# NEW-AQB-5-ANTON_TRANS-PWR_MotionControll.net
KiCad netlist of a schematic drawn in Altium Designer
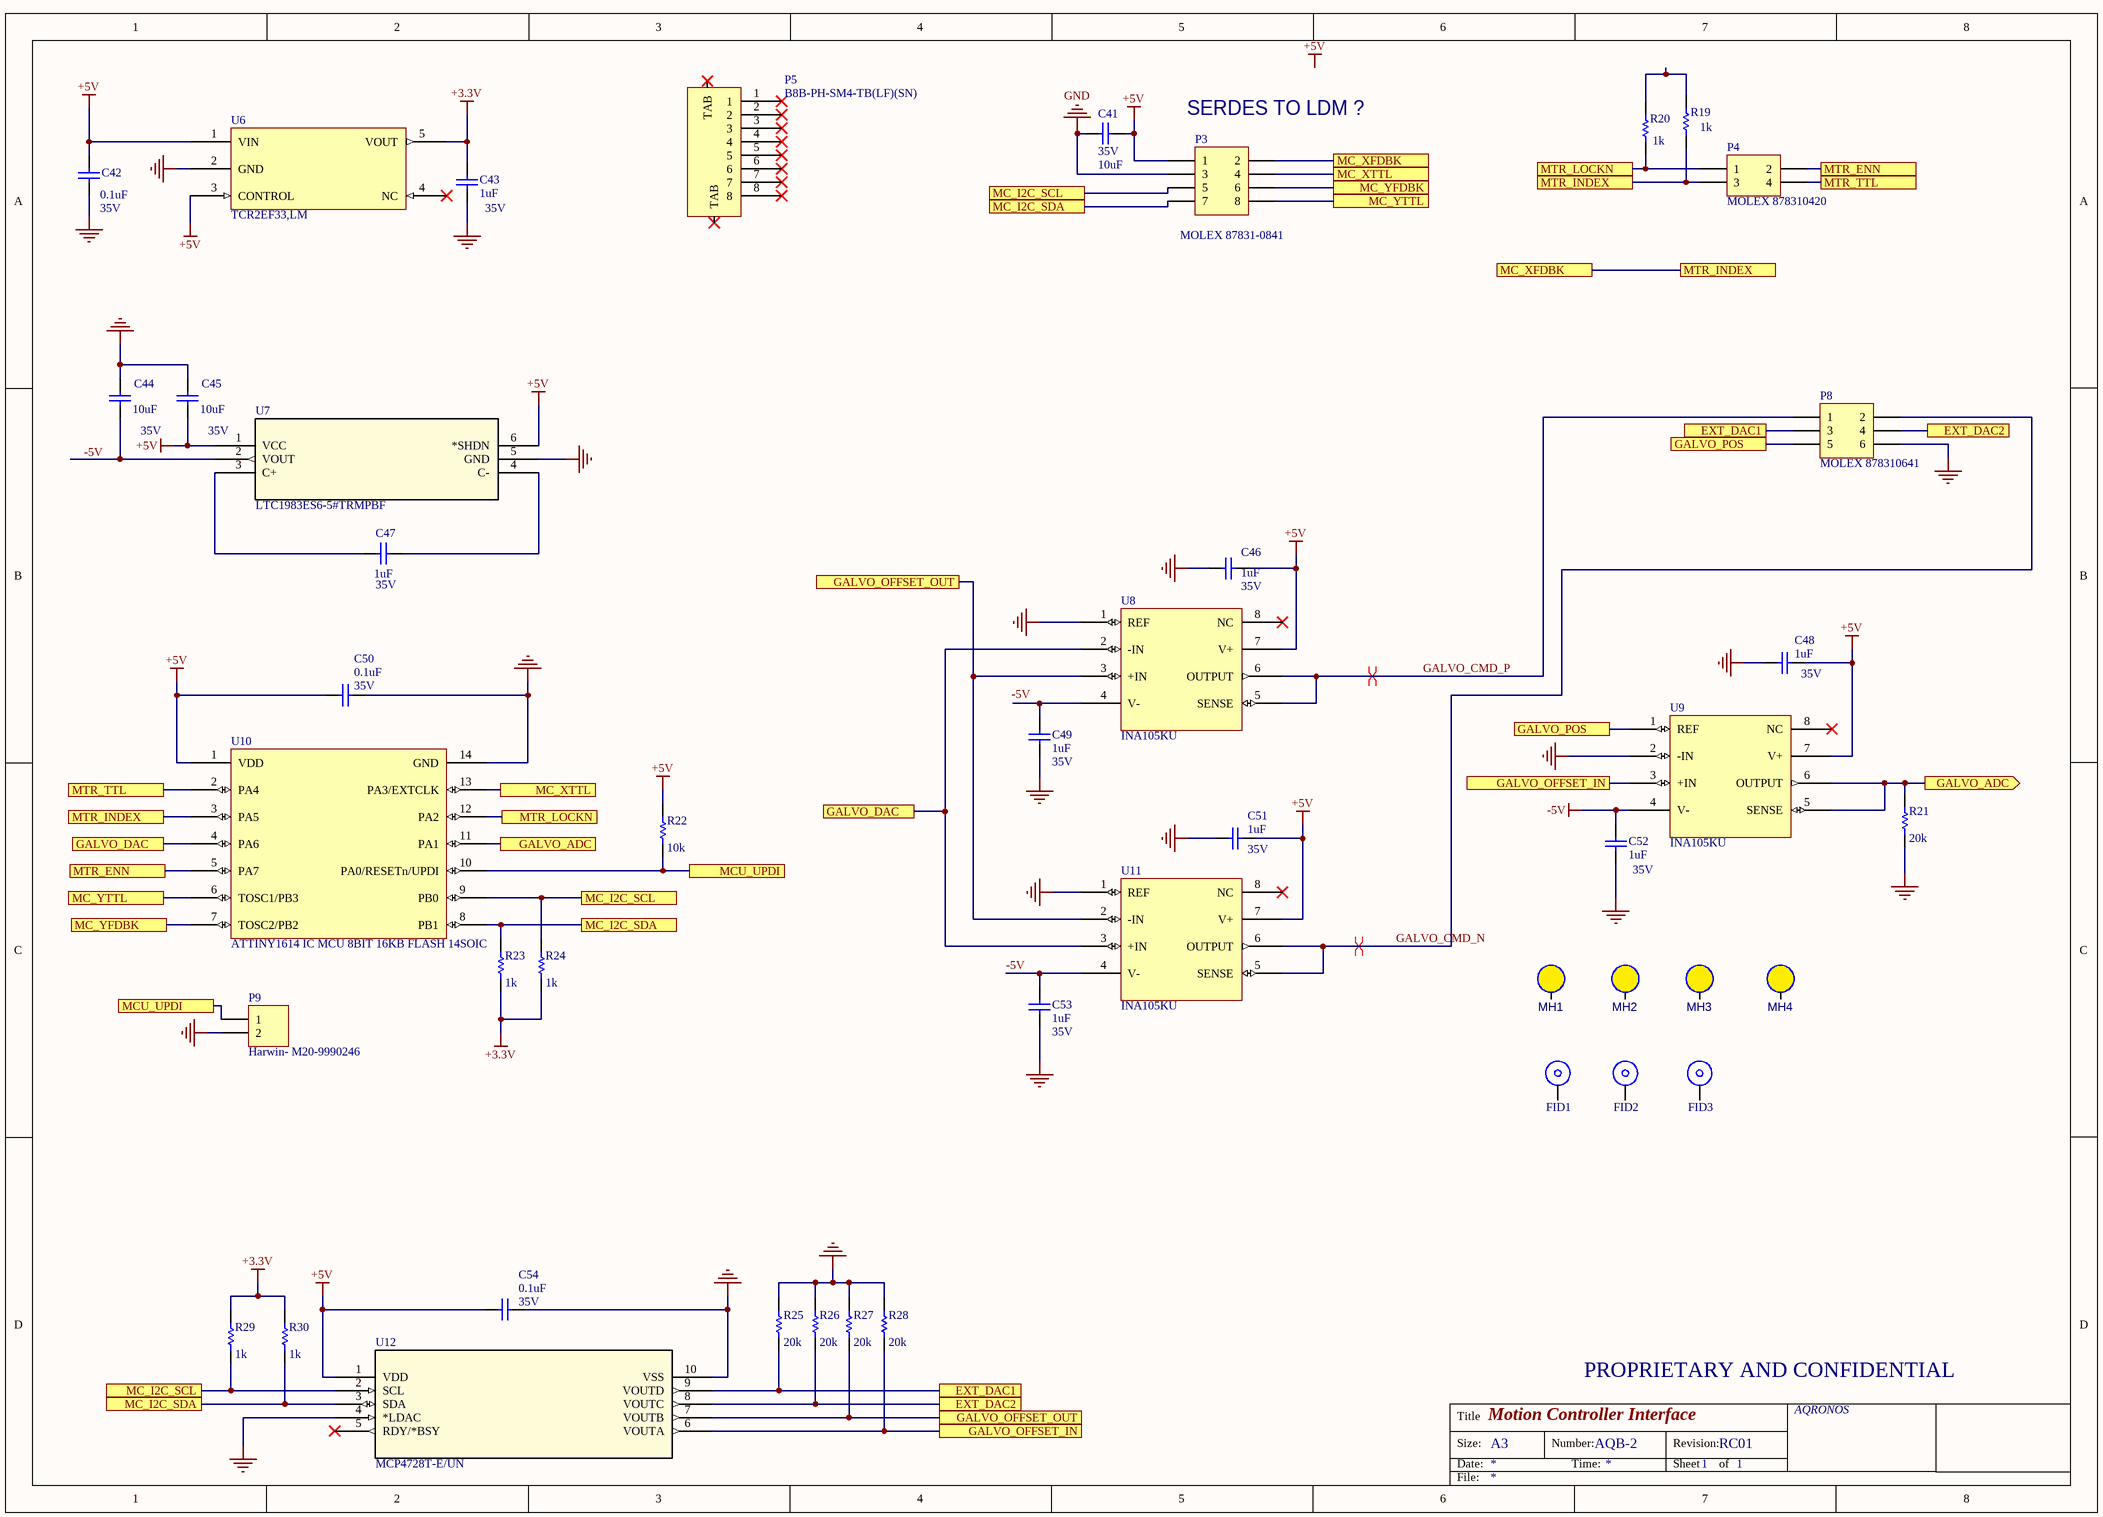
[diagram p0: NEW-AQB-5-ANTON_TRANS-PWR_MotionController.SchDoc]

(export (version "E")
  (design (tool "Eeschema 10.0.6"))
  (components
    (comp (ref "C41")
      (value "10uF")
      (footprint "CAP1206")
      (description "Capacitor_non_pol")
      (fields (field (name "MANUFACTURER PART NUMBER") "CGA5L1X7R1V106K160AC") (field (name "VOLTAGE") "35V"))
      (libsource (lib "AQRONOS_TEMP_SCH") (part "Capacitor_non_pol"))
    )
    (comp (ref "C42")
      (value "0.1uF")
      (footprint "CAP0402")
      (description "Capacitor_non_pol")
      (fields (field (name "MANUFACTURER PART NUMBER") "GMK107B7104KAHT") (field (name "VOLTAGE") "35V"))
      (libsource (lib "AQRONOS_TEMP_SCH") (part "Capacitor_non_pol"))
    )
    (comp (ref "C43")
      (value "1uF")
      (footprint "CAP0402")
      (description "Capacitor_non_pol")
      (fields (field (name "MANUFACTURER PART NUMBER") "GMK107AB7105KAHT") (field (name "VOLTAGE") "35V"))
      (libsource (lib "AQRONOS_TEMP_SCH") (part "Capacitor_non_pol"))
    )
    (comp (ref "C44")
      (value "10uF")
      (footprint "CAP1206")
      (description "Capacitor_non_pol")
      (fields (field (name "MANUFACTURER PART NUMBER") "CGA5L1X7R1V106K160AC") (field (name "VOLTAGE") "35V"))
      (libsource (lib "AQRONOS_TEMP_SCH") (part "Capacitor_non_pol"))
    )
    (comp (ref "C45")
      (value "10uF")
      (footprint "CAP1206")
      (description "Capacitor_non_pol")
      (fields (field (name "MANUFACTURER PART NUMBER") "CGA5L1X7R1V106K160AC") (field (name "VOLTAGE") "35V"))
      (libsource (lib "AQRONOS_TEMP_SCH") (part "Capacitor_non_pol"))
    )
    (comp (ref "C46")
      (value "1uF")
      (footprint "CAP0402")
      (description "Capacitor_non_pol")
      (fields (field (name "MANUFACTURER PART NUMBER") "GMK107AB7105KAHT") (field (name "VOLTAGE") "35V"))
      (libsource (lib "AQRONOS_TEMP_SCH") (part "Capacitor_non_pol"))
    )
    (comp (ref "C47")
      (value "1uF")
      (footprint "CAP0402")
      (description "Capacitor_non_pol")
      (fields (field (name "MANUFACTURER PART NUMBER") "GMK107AB7105KAHT") (field (name "VOLTAGE") "35V"))
      (libsource (lib "AQRONOS_TEMP_SCH") (part "Capacitor_non_pol"))
    )
    (comp (ref "C48")
      (value "1uF")
      (footprint "CAP0402")
      (description "Capacitor_non_pol")
      (fields (field (name "MANUFACTURER PART NUMBER") "GMK107AB7105KAHT") (field (name "VOLTAGE") "35V"))
      (libsource (lib "AQRONOS_TEMP_SCH") (part "Capacitor_non_pol"))
    )
    (comp (ref "C49")
      (value "1uF")
      (footprint "CAP0402")
      (description "Capacitor_non_pol")
      (fields (field (name "MANUFACTURER PART NUMBER") "GMK107AB7105KAHT") (field (name "VOLTAGE") "35V"))
      (libsource (lib "AQRONOS_TEMP_SCH") (part "Capacitor_non_pol"))
    )
    (comp (ref "C50")
      (value "0.1uF")
      (footprint "CAP0402")
      (description "Capacitor_non_pol")
      (fields (field (name "MANUFACTURER PART NUMBER") "GMK107B7104KAHT") (field (name "VOLTAGE") "35V"))
      (libsource (lib "AQRONOS_TEMP_SCH") (part "Capacitor_non_pol"))
    )
    (comp (ref "C51")
      (value "1uF")
      (footprint "CAP0402")
      (description "Capacitor_non_pol")
      (fields (field (name "MANUFACTURER PART NUMBER") "GMK107AB7105KAHT") (field (name "VOLTAGE") "35V"))
      (libsource (lib "AQRONOS_TEMP_SCH") (part "Capacitor_non_pol"))
    )
    (comp (ref "C52")
      (value "1uF")
      (footprint "CAP0402")
      (description "Capacitor_non_pol")
      (fields (field (name "MANUFACTURER PART NUMBER") "GMK107AB7105KAHT") (field (name "VOLTAGE") "35V"))
      (libsource (lib "AQRONOS_TEMP_SCH") (part "Capacitor_non_pol"))
    )
    (comp (ref "C53")
      (value "1uF")
      (footprint "CAP0402")
      (description "Capacitor_non_pol")
      (fields (field (name "MANUFACTURER PART NUMBER") "GMK107AB7105KAHT") (field (name "VOLTAGE") "35V"))
      (libsource (lib "AQRONOS_TEMP_SCH") (part "Capacitor_non_pol"))
    )
    (comp (ref "C54")
      (value "0.1uF")
      (footprint "CAP0402")
      (description "Capacitor_non_pol")
      (fields (field (name "MANUFACTURER PART NUMBER") "GMK107B7104KAHT") (field (name "VOLTAGE") "35V"))
      (libsource (lib "AQRONOS_TEMP_SCH") (part "Capacitor_non_pol"))
    )
    (comp (ref "FID1")
      (value "FIDUCIAL")
      (footprint "FID")
      (description "FID")
      (libsource (lib "AQRONOS-Released") (part "FID"))
    )
    (comp (ref "FID2")
      (value "FIDUCIAL")
      (footprint "FID")
      (description "FID")
      (libsource (lib "AQRONOS-Released") (part "FID"))
    )
    (comp (ref "FID3")
      (value "FIDUCIAL")
      (footprint "FID")
      (description "FID")
      (libsource (lib "AQRONOS-Released") (part "FID"))
    )
    (comp (ref "MH1")
      (value "PAD-MH")
      (footprint "PAD-135Mils")
      (description "PAD,MOUNTING HOLE")
      (libsource (lib "AQRONOS-Released") (part "PAD-MH"))
    )
    (comp (ref "MH2")
      (value "PAD-MH")
      (footprint "PAD-135Mils")
      (description "PAD,MOUNTING HOLE")
      (libsource (lib "AQRONOS-Released") (part "PAD-MH"))
    )
    (comp (ref "MH3")
      (value "PAD-MH")
      (footprint "PAD-135Mils")
      (description "PAD,MOUNTING HOLE")
      (libsource (lib "AQRONOS-Released") (part "PAD-MH"))
    )
    (comp (ref "MH4")
      (value "PAD-MH")
      (footprint "PAD-135Mils")
      (description "PAD,MOUNTING HOLE")
      (libsource (lib "AQRONOS-Released") (part "PAD-MH"))
    )
    (comp (ref "P3")
      (value "MOLEX 87831-0841")
      (footprint "HDR4X2-Molex")
      (description "Connector Header Through Hole 8 position 0.079\" (2.00mm)")
      (fields
        (field (name "DIGI-KEY PART NUMBER") "WM8611-ND")
        (field (name "MANUFACTURER PART NUMBER") "0878310841")
      )
      (libsource (lib "AQRONOS-Released") (part "HDR4x2-87831-0841"))
    )
    (comp (ref "P4")
      (value "MOLEX 878310420")
      (footprint "HDR2X2-Molex")
      (description "Connector Header Through Hole 4 position 0.079\" (2.00mm)")
      (fields
        (field (name "DIGI-KEY PART NUMBER") "WM18557-ND")
        (field (name "MANUFACTURER PART NUMBER") "87831-0420")
      )
      (libsource (lib "AQRONOS-Released") (part "HDR2x2-878310420"))
    )
    (comp (ref "P5")
      (value "B8B-PH-SM4-TB(LF)(SN)")
      (footprint "B8B-PH-SM4-TB(LF)(SN)")
      (description "8 PIN JST SMT 2.0 MM PITCH")
      (libsource (lib "AQRONOS_TEMP_SCH") (part "B8B-PH-SM4-TB(LF)(SN)"))
    )
    (comp (ref "P8")
      (value "MOLEX 878310641")
      (footprint "HDR3X2-Molex")
      (description "Connector Header Through Hole 6 position 0.079\" (2.00mm)")
      (fields
        (field (name "DIGI-KEY PART NUMBER") "WM3590-ND")
        (field (name "MANUFACTURER PART NUMBER") "878310641")
      )
      (libsource (lib "AQRONOS-Released") (part "HDR3x2-878310641"))
    )
    (comp (ref "P9")
      (value "Harwin- M20-9990246")
      (footprint "HDR1X2")
      (description "Connector Header Through Hole 2 position 0.100\" (2.54mm)")
      (fields
        (field (name "DIGI-KEY PART NUMBER") "952-2262-ND")
        (field (name "MANUFACTURER PART NUMBER") "M20-9990246")
      )
      (libsource (lib "AQRONOS-Released") (part "HDR1x2-M20-9990246"))
    )
    (comp (ref "R19")
      (value "1k")
      (footprint "RES0402")
      (description "Resistor")
      (fields (field (name "MANUFACTURER PART NUMBER") "ERJ-2GEJ102X"))
      (libsource (lib "AQRONOS_TEMP_SCH") (part "Resistor"))
    )
    (comp (ref "R20")
      (value "1k")
      (footprint "RES0402")
      (description "Resistor")
      (fields (field (name "MANUFACTURER PART NUMBER") "ERJ-2GEJ102X"))
      (libsource (lib "AQRONOS_TEMP_SCH") (part "Resistor"))
    )
    (comp (ref "R21")
      (value "20k")
      (footprint "RES0402")
      (description "Resistor")
      (fields (field (name "MANUFACTURER PART NUMBER") "ERJ-2RKF2002X"))
      (libsource (lib "AQRONOS_TEMP_SCH") (part "Resistor"))
    )
    (comp (ref "R22")
      (value "10k")
      (footprint "RES0402")
      (description "Resistor")
      (fields (field (name "MANUFACTURER PART NUMBER") "ERJ-2GEJ103X"))
      (libsource (lib "AQRONOS_TEMP_SCH") (part "Resistor"))
    )
    (comp (ref "R23")
      (value "1k")
      (footprint "RES0402")
      (description "Resistor")
      (fields (field (name "MANUFACTURER PART NUMBER") "ERJ-2GEJ102X"))
      (libsource (lib "AQRONOS_TEMP_SCH") (part "Resistor"))
    )
    (comp (ref "R24")
      (value "1k")
      (footprint "RES0402")
      (description "Resistor")
      (fields (field (name "MANUFACTURER PART NUMBER") "ERJ-2GEJ102X"))
      (libsource (lib "AQRONOS_TEMP_SCH") (part "Resistor"))
    )
    (comp (ref "R25")
      (value "20k")
      (footprint "RES0402")
      (description "Resistor")
      (fields (field (name "MANUFACTURER PART NUMBER") "ERJ-2RKF2002X"))
      (libsource (lib "AQRONOS_TEMP_SCH") (part "Resistor"))
    )
    (comp (ref "R26")
      (value "20k")
      (footprint "RES0402")
      (description "Resistor")
      (fields (field (name "MANUFACTURER PART NUMBER") "ERJ-2RKF2002X"))
      (libsource (lib "AQRONOS_TEMP_SCH") (part "Resistor"))
    )
    (comp (ref "R27")
      (value "20k")
      (footprint "RES0402")
      (description "Resistor")
      (fields (field (name "MANUFACTURER PART NUMBER") "ERJ-2RKF2002X"))
      (libsource (lib "AQRONOS_TEMP_SCH") (part "Resistor"))
    )
    (comp (ref "R28")
      (value "20k")
      (footprint "RES0402")
      (description "Resistor")
      (fields (field (name "MANUFACTURER PART NUMBER") "ERJ-2RKF2002X"))
      (libsource (lib "AQRONOS_TEMP_SCH") (part "Resistor"))
    )
    (comp (ref "R29")
      (value "1k")
      (footprint "RES0402")
      (description "Resistor")
      (fields (field (name "MANUFACTURER PART NUMBER") "ERJ-2GEJ102X"))
      (libsource (lib "AQRONOS_TEMP_SCH") (part "Resistor"))
    )
    (comp (ref "R30")
      (value "1k")
      (footprint "RES0402")
      (description "Resistor")
      (fields (field (name "MANUFACTURER PART NUMBER") "ERJ-2GEJ102X"))
      (libsource (lib "AQRONOS_TEMP_SCH") (part "Resistor"))
    )
    (comp (ref "U6")
      (value "TCR2EF33,LM")
      (footprint "SOT-753")
      (description "Linear Voltage Regulator IC Positive Fixed 1 Output 200mA SMV")
      (fields
        (field (name "DIGIKEY PART NUMBER") "TCR2EF33LM(CTTR-ND")
        (field (name "MANUFACTURER PART NUMBER") "TCR2EF33,LM(CT")
      )
      (libsource (lib "AQRONOS-Released") (part "TCR2EF33,LM"))
    )
    (comp (ref "U7")
      (value "LTC1983ES6-5#TRMPBF")
      (footprint "SOT-23-6")
      (description "Charge Pump Switching Regulator IC Negative Fixed -5V 1 Output 100mA SOT-23-6 Thin, TSOT-23-6")
      (fields (field (name "DIGI-KEY PART NUMBER") "LTC1983ES6-5#TRMPBFTR-ND"))
      (libsource (lib "AQRONOS-Released") (part "LTC1983ES6-5#TRM"))
    )
    (comp (ref "U8")
      (value "INA105KU")
      (footprint "SOIC8")
      (description "IC OPAMP DIFFERENTIAL 1MHZ 8SOIC")
      (fields (field (name "DIGI-KEY PART NUMBER") "296-44407-5-ND"))
      (libsource (lib "AQRONOS-Released") (part "INA105"))
    )
    (comp (ref "U9")
      (value "INA105KU")
      (footprint "SOIC8")
      (description "IC OPAMP DIFFERENTIAL 1MHZ 8SOIC")
      (fields (field (name "DIGI-KEY PART NUMBER") "296-44407-5-ND"))
      (libsource (lib "AQRONOS-Released") (part "INA105"))
    )
    (comp (ref "U10")
      (value "ATTINY1614 IC MCU 8BIT 16KB FLASH 14SOIC")
      (footprint "SOIC14")
      (description "AVR tinyAVR™ 1 Microcontroller IC 8-Bit 20MHz 16KB (16K x 8) FLASH 14-SOIC")
      (fields
        (field (name "DIGI-KEY PART NUMBER") "ATTINY1614-SSFRCT-ND")
        (field (name "MANUFACTURER PART NUMBER") "ATTINY1614-SSFR")
      )
      (libsource (lib "AQRONOS-Released") (part "ATTINY1614-SSFR"))
    )
    (comp (ref "U11")
      (value "INA105KU")
      (footprint "SOIC8")
      (description "IC OPAMP DIFFERENTIAL 1MHZ 8SOIC")
      (fields (field (name "DIGI-KEY PART NUMBER") "296-44407-5-ND"))
      (libsource (lib "AQRONOS-Released") (part "INA105"))
    )
    (comp (ref "U12")
      (value "MCP4728T-E/UN")
      (footprint "MSOP10")
      (description "12 Bit Digital to Analog Converter 4 10-MSOP")
      (fields (field (name "DIGI-KEY PART NUMBER") "MCP4728T-E/UNTR-ND"))
      (libsource (lib "AQRONOS-Released") (part "MCP4728T-E/UN"))
    )
  )
  (nets
    (net (code "1") (name "+3.3V") (class "Default")
      (node (ref "C43") (pin "1") (pinfunction "1_1") (pintype "passive"))
      (node (ref "R23") (pin "1") (pinfunction "1_1") (pintype "passive"))
      (node (ref "R24") (pin "1") (pinfunction "1_1") (pintype "passive"))
      (node (ref "R29") (pin "2") (pinfunction "2_2") (pintype "passive"))
      (node (ref "R30") (pin "2") (pinfunction "2_2") (pintype "passive"))
      (node (ref "U6") (pin "5") (pinfunction "VOUT_5") (pintype "output"))
    )
    (net (code "2") (name "+5V") (class "Default")
      (node (ref "C41") (pin "2") (pinfunction "2_2") (pintype "passive"))
      (node (ref "C42") (pin "1") (pinfunction "1_1") (pintype "passive"))
      (node (ref "C45") (pin "2") (pinfunction "2_2") (pintype "passive"))
      (node (ref "C46") (pin "2") (pinfunction "2_2") (pintype "passive"))
      (node (ref "C48") (pin "2") (pinfunction "2_2") (pintype "passive"))
      (node (ref "C50") (pin "2") (pinfunction "2_2") (pintype "passive"))
      (node (ref "C51") (pin "2") (pinfunction "2_2") (pintype "passive"))
      (node (ref "C54") (pin "2") (pinfunction "2_2") (pintype "passive"))
      (node (ref "P3") (pin "1") (pinfunction "1_1") (pintype "passive"))
      (node (ref "R22") (pin "2") (pinfunction "2_2") (pintype "passive"))
      (node (ref "U10") (pin "1") (pinfunction "VDD_1") (pintype "power_in"))
      (node (ref "U11") (pin "7") (pinfunction "V+_7") (pintype "power_in"))
      (node (ref "U12") (pin "1") (pinfunction "VDD_1") (pintype "power_in"))
      (node (ref "U6") (pin "1") (pinfunction "VIN_1") (pintype "power_in"))
      (node (ref "U6") (pin "3") (pinfunction "CONTROL_3") (pintype "input"))
      (node (ref "U7") (pin "1") (pinfunction "VCC_1") (pintype "power_in"))
      (node (ref "U7") (pin "6") (pinfunction "*SHDN_6") (pintype "passive"))
      (node (ref "U8") (pin "7") (pinfunction "V+_7") (pintype "power_in"))
      (node (ref "U9") (pin "7") (pinfunction "V+_7") (pintype "power_in"))
    )
    (net (code "3") (name "-5V") (class "Default")
      (node (ref "C52") (pin "1") (pinfunction "1_1") (pintype "passive"))
      (node (ref "C53") (pin "1") (pinfunction "1_1") (pintype "passive"))
      (node (ref "U11") (pin "4") (pinfunction "V-_4") (pintype "power_in"))
      (node (ref "U9") (pin "4") (pinfunction "V-_4") (pintype "power_in"))
    )
    (net (code "4") (name "/EXT_DAC1") (class "Default")
      (node (ref "P8") (pin "3") (pinfunction "3_3") (pintype "passive"))
      (node (ref "R25") (pin "1") (pinfunction "1_1") (pintype "passive"))
      (node (ref "U12") (pin "9") (pinfunction "VOUTD_9") (pintype "output"))
    )
    (net (code "5") (name "/EXT_DAC2") (class "Default")
      (node (ref "P8") (pin "4") (pinfunction "4_4") (pintype "passive"))
      (node (ref "R26") (pin "1") (pinfunction "1_1") (pintype "passive"))
      (node (ref "U12") (pin "8") (pinfunction "VOUTC_8") (pintype "output"))
    )
    (net (code "6") (name "/GALVO_ADC") (class "Default")
      (node (ref "R21") (pin "2") (pinfunction "2_2") (pintype "passive"))
      (node (ref "U10") (pin "11") (pinfunction "PA1_11") (pintype "bidirectional"))
      (node (ref "U9") (pin "5") (pinfunction "SENSE_5") (pintype "bidirectional"))
      (node (ref "U9") (pin "6") (pinfunction "OUTPUT_6") (pintype "output"))
    )
    (net (code "7") (name "/GALVO_CMD_N") (class "Default")
      (node (ref "P8") (pin "2") (pinfunction "2_2") (pintype "passive"))
      (node (ref "U11") (pin "5") (pinfunction "SENSE_5") (pintype "bidirectional"))
      (node (ref "U11") (pin "6") (pinfunction "OUTPUT_6") (pintype "output"))
    )
    (net (code "8") (name "/GALVO_CMD_P") (class "Default")
      (node (ref "P8") (pin "1") (pinfunction "1_1") (pintype "passive"))
      (node (ref "U8") (pin "5") (pinfunction "SENSE_5") (pintype "bidirectional"))
      (node (ref "U8") (pin "6") (pinfunction "OUTPUT_6") (pintype "output"))
    )
    (net (code "9") (name "/GALVO_DAC") (class "Default")
      (node (ref "U10") (pin "4") (pinfunction "PA6_4") (pintype "bidirectional"))
      (node (ref "U11") (pin "3") (pinfunction "+IN_3") (pintype "bidirectional"))
      (node (ref "U8") (pin "2") (pinfunction "-IN_2") (pintype "bidirectional"))
    )
    (net (code "10") (name "/GALVO_OFFSET_IN") (class "Default")
      (node (ref "R28") (pin "1") (pinfunction "1_1") (pintype "passive"))
      (node (ref "U12") (pin "6") (pinfunction "VOUTA_6") (pintype "output"))
      (node (ref "U9") (pin "3") (pinfunction "+IN_3") (pintype "bidirectional"))
    )
    (net (code "11") (name "/GALVO_OFFSET_OUT") (class "Default")
      (node (ref "R27") (pin "1") (pinfunction "1_1") (pintype "passive"))
      (node (ref "U11") (pin "2") (pinfunction "-IN_2") (pintype "bidirectional"))
      (node (ref "U12") (pin "7") (pinfunction "VOUTB_7") (pintype "output"))
      (node (ref "U8") (pin "3") (pinfunction "+IN_3") (pintype "bidirectional"))
    )
    (net (code "12") (name "/GALVO_POS") (class "Default")
      (node (ref "P8") (pin "5") (pinfunction "5_5") (pintype "passive"))
      (node (ref "U9") (pin "1") (pinfunction "REF_1") (pintype "bidirectional"))
    )
    (net (code "13") (name "/MCU_UPDI") (class "Default")
      (node (ref "P9") (pin "1") (pinfunction "1_1") (pintype "passive"))
      (node (ref "R22") (pin "1") (pinfunction "1_1") (pintype "passive"))
      (node (ref "U10") (pin "10") (pinfunction "PA0/RESETn/UPDI_10") (pintype "bidirectional"))
    )
    (net (code "14") (name "/MC_I2C_SCL") (class "Default")
      (node (ref "P3") (pin "5") (pinfunction "5_5") (pintype "passive"))
      (node (ref "R24") (pin "2") (pinfunction "2_2") (pintype "passive"))
      (node (ref "R29") (pin "1") (pinfunction "1_1") (pintype "passive"))
      (node (ref "U10") (pin "9") (pinfunction "PB0_9") (pintype "bidirectional"))
      (node (ref "U12") (pin "2") (pinfunction "SCL_2") (pintype "input"))
    )
    (net (code "15") (name "/MC_I2C_SDA") (class "Default")
      (node (ref "P3") (pin "7") (pinfunction "7_7") (pintype "passive"))
      (node (ref "R23") (pin "2") (pinfunction "2_2") (pintype "passive"))
      (node (ref "R30") (pin "1") (pinfunction "1_1") (pintype "passive"))
      (node (ref "U10") (pin "8") (pinfunction "PB1_8") (pintype "bidirectional"))
      (node (ref "U12") (pin "3") (pinfunction "SDA_3") (pintype "bidirectional"))
    )
    (net (code "16") (name "/MC_XFDBK") (class "Default")
      (node (ref "P3") (pin "2") (pinfunction "2_2") (pintype "passive"))
      (node (ref "P4") (pin "3") (pinfunction "3_3") (pintype "passive"))
      (node (ref "R19") (pin "1") (pinfunction "1_1") (pintype "passive"))
      (node (ref "U10") (pin "3") (pinfunction "PA5_3") (pintype "bidirectional"))
    )
    (net (code "17") (name "/MC_XTTL") (class "Default")
      (node (ref "P3") (pin "4") (pinfunction "4_4") (pintype "passive"))
      (node (ref "U10") (pin "13") (pinfunction "PA3/EXTCLK_13") (pintype "bidirectional"))
    )
    (net (code "18") (name "/MC_YFDBK") (class "Default")
      (node (ref "P3") (pin "6") (pinfunction "6_6") (pintype "passive"))
      (node (ref "U10") (pin "7") (pinfunction "TOSC2/PB2_7") (pintype "bidirectional"))
    )
    (net (code "19") (name "/MC_YTTL") (class "Default")
      (node (ref "P3") (pin "8") (pinfunction "8_8") (pintype "passive"))
      (node (ref "U10") (pin "6") (pinfunction "TOSC1/PB3_6") (pintype "bidirectional"))
    )
    (net (code "20") (name "/MTR_ENN") (class "Default")
      (node (ref "P4") (pin "2") (pinfunction "2_2") (pintype "passive"))
      (node (ref "U10") (pin "5") (pinfunction "PA7_5") (pintype "bidirectional"))
    )
    (net (code "21") (name "/MTR_LOCKN") (class "Default")
      (node (ref "P4") (pin "1") (pinfunction "1_1") (pintype "passive"))
      (node (ref "R20") (pin "1") (pinfunction "1_1") (pintype "passive"))
      (node (ref "U10") (pin "12") (pinfunction "PA2_12") (pintype "bidirectional"))
    )
    (net (code "22") (name "/MTR_TTL") (class "Default")
      (node (ref "P4") (pin "4") (pinfunction "4_4") (pintype "passive"))
      (node (ref "U10") (pin "2") (pinfunction "PA4_2") (pintype "bidirectional"))
    )
    (net (code "23") (name "GND") (class "Default")
      (node (ref "C41") (pin "1") (pinfunction "1_1") (pintype "passive"))
      (node (ref "C42") (pin "2") (pinfunction "2_2") (pintype "passive"))
      (node (ref "C43") (pin "2") (pinfunction "2_2") (pintype "passive"))
      (node (ref "C44") (pin "1") (pinfunction "1_1") (pintype "passive"))
      (node (ref "C45") (pin "1") (pinfunction "1_1") (pintype "passive"))
      (node (ref "C46") (pin "1") (pinfunction "1_1") (pintype "passive"))
      (node (ref "C48") (pin "1") (pinfunction "1_1") (pintype "passive"))
      (node (ref "C49") (pin "2") (pinfunction "2_2") (pintype "passive"))
      (node (ref "C50") (pin "1") (pinfunction "1_1") (pintype "passive"))
      (node (ref "C51") (pin "1") (pinfunction "1_1") (pintype "passive"))
      (node (ref "C52") (pin "2") (pinfunction "2_2") (pintype "passive"))
      (node (ref "C53") (pin "2") (pinfunction "2_2") (pintype "passive"))
      (node (ref "C54") (pin "1") (pinfunction "1_1") (pintype "passive"))
      (node (ref "P3") (pin "3") (pinfunction "3_3") (pintype "passive"))
      (node (ref "P8") (pin "6") (pinfunction "6_6") (pintype "passive"))
      (node (ref "P9") (pin "2") (pinfunction "2_2") (pintype "passive"))
      (node (ref "R21") (pin "1") (pinfunction "1_1") (pintype "passive"))
      (node (ref "R25") (pin "2") (pinfunction "2_2") (pintype "passive"))
      (node (ref "R26") (pin "2") (pinfunction "2_2") (pintype "passive"))
      (node (ref "R27") (pin "2") (pinfunction "2_2") (pintype "passive"))
      (node (ref "R28") (pin "2") (pinfunction "2_2") (pintype "passive"))
      (node (ref "U10") (pin "14") (pinfunction "GND_14") (pintype "power_in"))
      (node (ref "U11") (pin "1") (pinfunction "REF_1") (pintype "bidirectional"))
      (node (ref "U12") (pin "10") (pinfunction "VSS_10") (pintype "power_in"))
      (node (ref "U12") (pin "4") (pinfunction "*LDAC_4") (pintype "input"))
      (node (ref "U6") (pin "2") (pinfunction "GND_2") (pintype "power_in"))
      (node (ref "U7") (pin "5") (pinfunction "GND_5") (pintype "power_in"))
      (node (ref "U8") (pin "1") (pinfunction "REF_1") (pintype "bidirectional"))
      (node (ref "U9") (pin "2") (pinfunction "-IN_2") (pintype "bidirectional"))
    )
    (net (code "24") (name "Net-(R19-Pad2)") (class "Default")
      (node (ref "R19") (pin "2") (pinfunction "2_2") (pintype "passive"))
      (node (ref "R20") (pin "2") (pinfunction "2_2") (pintype "passive"))
    )
    (net (code "25") (name "Net-(U7-C+)") (class "Default")
      (node (ref "C47") (pin "1") (pinfunction "1_1") (pintype "passive"))
      (node (ref "U7") (pin "3") (pinfunction "C+_3") (pintype "passive"))
    )
    (net (code "26") (name "Net-(U7-C-)") (class "Default")
      (node (ref "C47") (pin "2") (pinfunction "2_2") (pintype "passive"))
      (node (ref "U7") (pin "4") (pinfunction "C-_4") (pintype "passive"))
    )
    (net (code "27") (name "Net-(U7-VOUT)") (class "Default")
      (node (ref "C44") (pin "2") (pinfunction "2_2") (pintype "passive"))
      (node (ref "U7") (pin "2") (pinfunction "VOUT_2") (pintype "output"))
    )
    (net (code "28") (name "Net-(U8-V-)") (class "Default")
      (node (ref "C49") (pin "1") (pinfunction "1_1") (pintype "passive"))
      (node (ref "U8") (pin "4") (pinfunction "V-_4") (pintype "power_in"))
    )
    (net (code "29") (name "unconnected-(MH1-Pad1)") (class "Default")
      (node (ref "MH1") (pin "1") (pintype "passive"))
    )
    (net (code "30") (name "unconnected-(MH2-Pad1)") (class "Default")
      (node (ref "MH2") (pin "1") (pintype "passive"))
    )
    (net (code "31") (name "unconnected-(MH3-Pad1)") (class "Default")
      (node (ref "MH3") (pin "1") (pintype "passive"))
    )
    (net (code "32") (name "unconnected-(MH4-Pad1)") (class "Default")
      (node (ref "MH4") (pin "1") (pintype "passive"))
    )
    (net (code "33") (name "unconnected-(P5-Pad1)") (class "Default")
      (node (ref "P5") (pin "1") (pinfunction "1_1") (pintype "passive+no_connect"))
    )
    (net (code "34") (name "unconnected-(P5-Pad2)") (class "Default")
      (node (ref "P5") (pin "2") (pinfunction "2_2") (pintype "passive+no_connect"))
    )
    (net (code "35") (name "unconnected-(P5-Pad3)") (class "Default")
      (node (ref "P5") (pin "3") (pinfunction "3_3") (pintype "passive+no_connect"))
    )
    (net (code "36") (name "unconnected-(P5-Pad4)") (class "Default")
      (node (ref "P5") (pin "4") (pinfunction "4_4") (pintype "passive+no_connect"))
    )
    (net (code "37") (name "unconnected-(P5-Pad5)") (class "Default")
      (node (ref "P5") (pin "5") (pinfunction "5_5") (pintype "passive+no_connect"))
    )
    (net (code "38") (name "unconnected-(P5-Pad6)") (class "Default")
      (node (ref "P5") (pin "6") (pinfunction "6_6") (pintype "passive+no_connect"))
    )
    (net (code "39") (name "unconnected-(P5-Pad7)") (class "Default")
      (node (ref "P5") (pin "7") (pinfunction "7_7") (pintype "passive+no_connect"))
    )
    (net (code "40") (name "unconnected-(P5-Pad8)") (class "Default")
      (node (ref "P5") (pin "8") (pinfunction "8_8") (pintype "passive+no_connect"))
    )
    (net (code "41") (name "unconnected-(P5-PadTAB)") (class "Default")
      (node (ref "P5") (pin "TAB") (pinfunction "TAB_TAB") (pintype "passive+no_connect"))
    )
    (net (code "42") (name "unconnected-(P5-PadTAB)_1") (class "Default")
      (node (ref "P5") (pin "TAB") (pinfunction "TAB_TAB") (pintype "passive+no_connect"))
    )
    (net (code "43") (name "unconnected-(U6-NC-Pad4)") (class "Default")
      (node (ref "U6") (pin "4") (pinfunction "NC_4") (pintype "input+no_connect"))
    )
    (net (code "44") (name "unconnected-(U8-NC-Pad8)") (class "Default")
      (node (ref "U8") (pin "8") (pinfunction "NC_8") (pintype "tri_state+no_connect"))
    )
    (net (code "45") (name "unconnected-(U9-NC-Pad8)") (class "Default")
      (node (ref "U9") (pin "8") (pinfunction "NC_8") (pintype "tri_state+no_connect"))
    )
    (net (code "46") (name "unconnected-(U11-NC-Pad8)") (class "Default")
      (node (ref "U11") (pin "8") (pinfunction "NC_8") (pintype "tri_state+no_connect"))
    )
    (net (code "47") (name "unconnected-(U12-RDY{slash}*BSY-Pad5)") (class "Default")
      (node (ref "U12") (pin "5") (pinfunction "RDY/*BSY_5") (pintype "output+no_connect"))
    )
  )
)
